# smarticle12.net
KiCad netlist of a schematic drawn in EAGLE
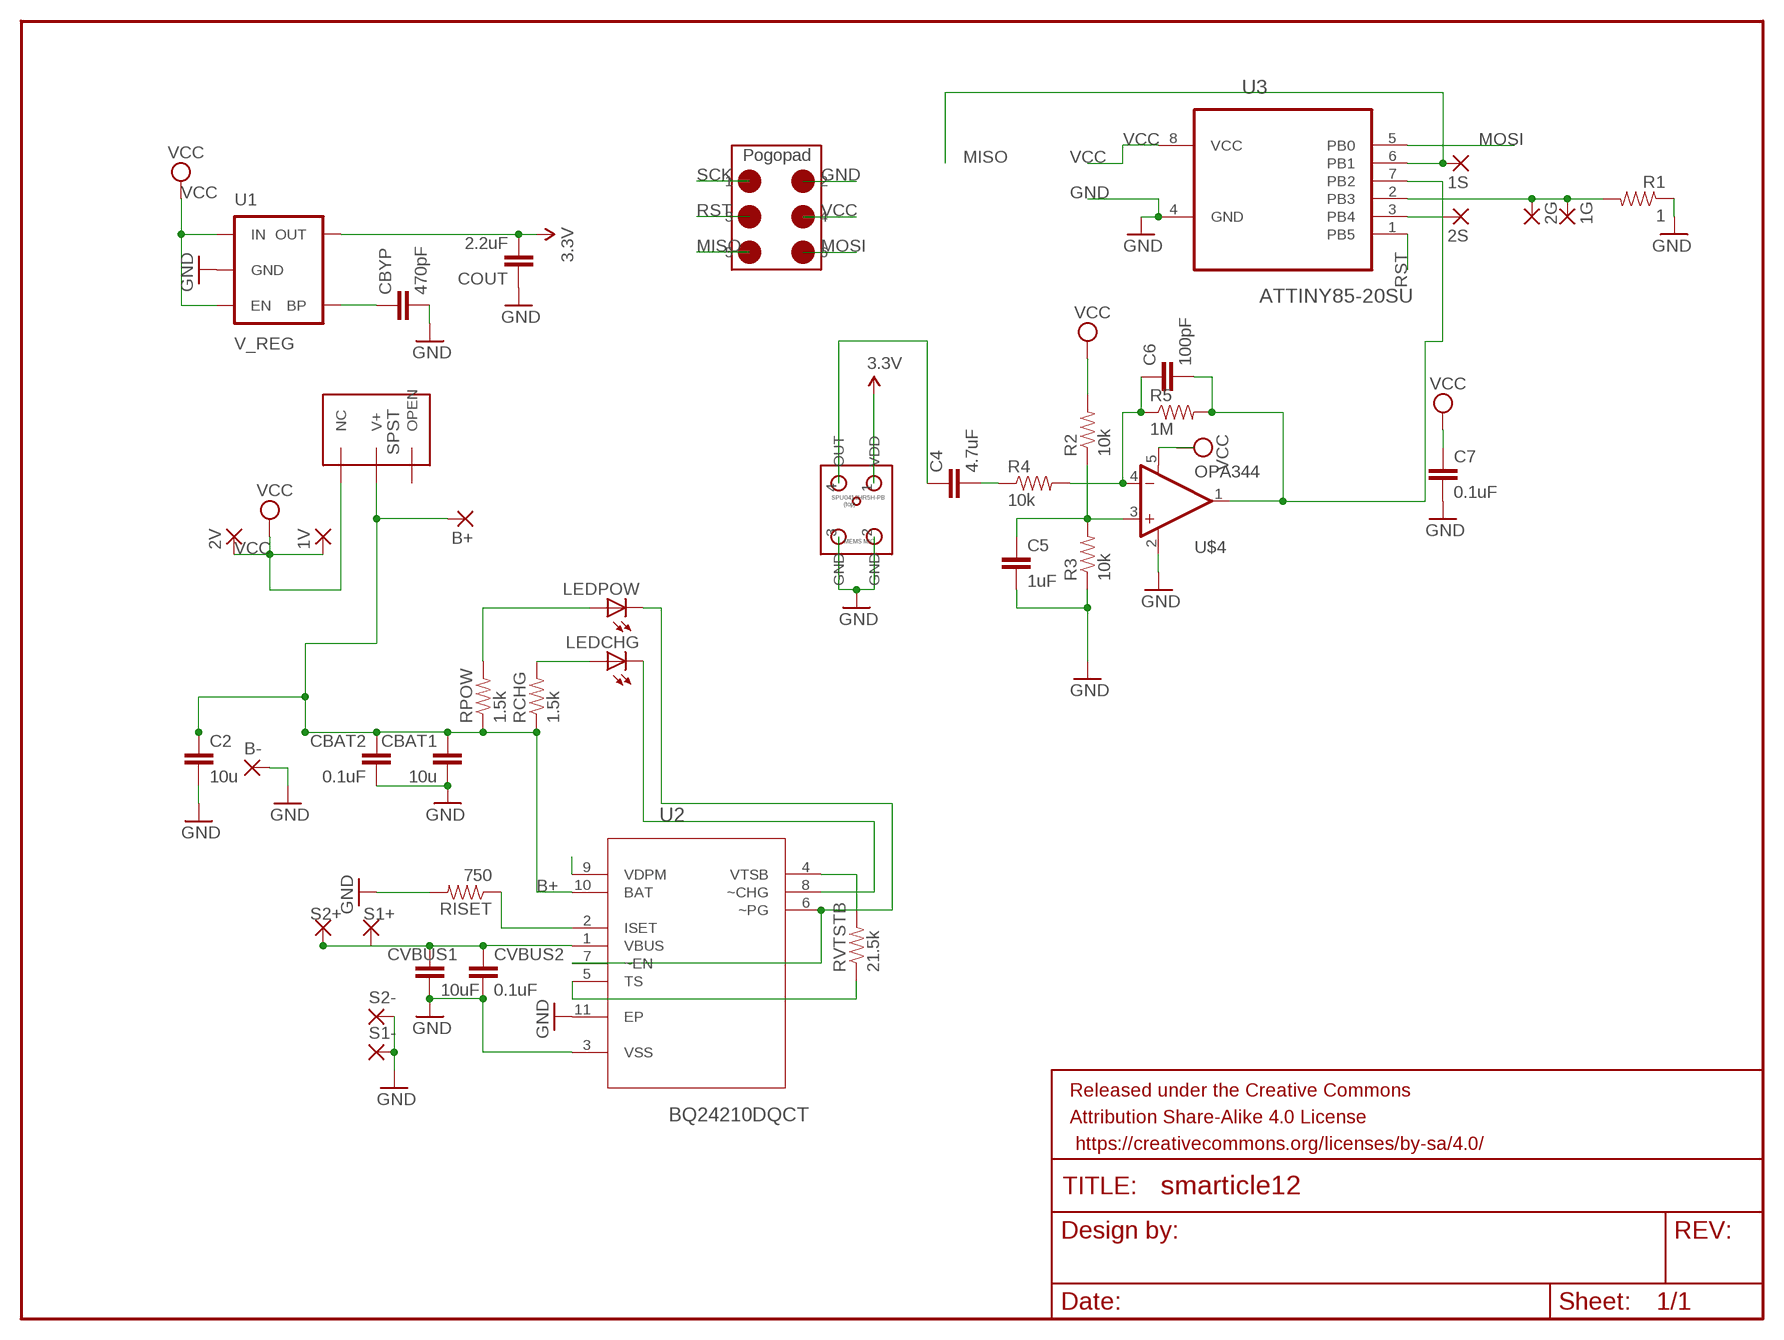
[diagram p0: schematic, sheet 1]

(export (version "E")
  (design (tool "Eeschema 10.0.6"))
  (components
    (comp (ref "1G")
      (value "1,6/0,8")
      (footprint "eagle-import:1,6_0,8")
      (libsource (lib "eagle-import") (part "1,6/0,8"))
    )
    (comp (ref "1S")
      (value "1,6/0,8")
      (footprint "eagle-import:1,6_0,8")
      (libsource (lib "eagle-import") (part "1,6/0,8"))
    )
    (comp (ref "1V")
      (value "1,6/0,8")
      (footprint "eagle-import:1,6_0,8")
      (libsource (lib "eagle-import") (part "1,6/0,8"))
    )
    (comp (ref "2G")
      (value "1,6/0,8")
      (footprint "eagle-import:1,6_0,8")
      (libsource (lib "eagle-import") (part "1,6/0,8"))
    )
    (comp (ref "2S")
      (value "1,6/0,8")
      (footprint "eagle-import:1,6_0,8")
      (libsource (lib "eagle-import") (part "1,6/0,8"))
    )
    (comp (ref "2V")
      (value "1,6/0,8")
      (footprint "eagle-import:1,6_0,8")
      (libsource (lib "eagle-import") (part "1,6/0,8"))
    )
    (comp (ref "B+")
      (value "1,6/0,8")
      (footprint "eagle-import:1,6_0,8")
      (libsource (lib "eagle-import") (part "1,6/0,8"))
    )
    (comp (ref "B-")
      (value "1,6/0,8")
      (footprint "eagle-import:1,6_0,8")
      (libsource (lib "eagle-import") (part "1,6/0,8"))
    )
    (comp (ref "C2")
      (value "10u")
      (footprint "eagle-import:0603-CAP")
      (libsource (lib "eagle-import") (part "CAP0603-CAP"))
    )
    (comp (ref "C4")
      (value "4.7uF")
      (footprint "eagle-import:0603-CAP")
      (libsource (lib "eagle-import") (part "CAP0603-CAP"))
    )
    (comp (ref "C5")
      (value "1uF")
      (footprint "eagle-import:0603-CAP")
      (libsource (lib "eagle-import") (part "CAP0603-CAP"))
    )
    (comp (ref "C6")
      (value "100pF")
      (footprint "eagle-import:0603-CAP")
      (libsource (lib "eagle-import") (part "CAP0603-CAP"))
    )
    (comp (ref "C7")
      (value "0.1uF")
      (footprint "eagle-import:0603-CAP")
      (libsource (lib "eagle-import") (part "CAP0603-CAP"))
    )
    (comp (ref "CBAT1")
      (value "10u")
      (footprint "eagle-import:0805")
      (libsource (lib "eagle-import") (part "CAP0805"))
    )
    (comp (ref "CBAT2")
      (value "0.1uF")
      (footprint "eagle-import:0603-CAP")
      (libsource (lib "eagle-import") (part "CAP0603-CAP"))
    )
    (comp (ref "CBYP")
      (value "470pF")
      (footprint "eagle-import:0603-CAP")
      (libsource (lib "eagle-import") (part "CAP0603-CAP"))
    )
    (comp (ref "COUT")
      (value "2.2uF")
      (footprint "eagle-import:0603-CAP")
      (libsource (lib "eagle-import") (part "CAP0603-CAP"))
    )
    (comp (ref "CVBUS1")
      (value "10uF")
      (footprint "eagle-import:1206")
      (libsource (lib "eagle-import") (part "CAP1206"))
    )
    (comp (ref "CVBUS2")
      (value "0.1uF")
      (footprint "eagle-import:0603-CAP")
      (libsource (lib "eagle-import") (part "CAP0603-CAP"))
    )
    (comp (ref "FRAME1")
      (value "FRAME-LETTERNO_PACKAGE")
      (footprint "eagle-import:DUMMY")
      (fields (field (name "DESIGNER") "Nobody"))
      (libsource (lib "eagle-import") (part "FRAME-LETTERNO_PACKAGE"))
    )
    (comp (ref "LEDCHG")
      (value "LEDCHIPLED_0603")
      (footprint "eagle-import:CHIPLED_0603")
      (libsource (lib "eagle-import") (part "LEDCHIPLED_0603"))
    )
    (comp (ref "LEDPOW")
      (value "LEDCHIPLED_0603")
      (footprint "eagle-import:CHIPLED_0603")
      (libsource (lib "eagle-import") (part "LEDCHIPLED_0603"))
    )
    (comp (ref "R1")
      (value "1")
      (footprint "eagle-import:0805")
      (libsource (lib "eagle-import") (part "SparkFun-Resistors_RESISTOR0805-RES"))
    )
    (comp (ref "R2")
      (value "10k")
      (footprint "eagle-import:0603-RES")
      (libsource (lib "eagle-import") (part "RESISTOR0603-RES"))
    )
    (comp (ref "R3")
      (value "10k")
      (footprint "eagle-import:0603-RES")
      (libsource (lib "eagle-import") (part "RESISTOR0603-RES"))
    )
    (comp (ref "R4")
      (value "10k")
      (footprint "eagle-import:0603-RES")
      (libsource (lib "eagle-import") (part "RESISTOR0603-RES"))
    )
    (comp (ref "R5")
      (value "1M")
      (footprint "eagle-import:0603-RES")
      (libsource (lib "eagle-import") (part "RESISTOR0603-RES"))
    )
    (comp (ref "RCHG")
      (value "1.5k")
      (footprint "eagle-import:0603-RES")
      (libsource (lib "eagle-import") (part "RESISTOR0603-RES"))
    )
    (comp (ref "RISET")
      (value "750")
      (footprint "eagle-import:0603-RES")
      (libsource (lib "eagle-import") (part "RESISTOR0603-RES"))
    )
    (comp (ref "RPOW")
      (value "1.5k")
      (footprint "eagle-import:0603-RES")
      (libsource (lib "eagle-import") (part "RESISTOR0603-RES"))
    )
    (comp (ref "RVTSTB")
      (value "21.5k")
      (footprint "eagle-import:0603-RES")
      (libsource (lib "eagle-import") (part "RESISTOR0603-RES"))
    )
    (comp (ref "S1+")
      (value "1,6/0,8")
      (footprint "eagle-import:1,6_0,8")
      (libsource (lib "eagle-import") (part "1,6/0,8"))
    )
    (comp (ref "S1-")
      (value "1,6/0,8")
      (footprint "eagle-import:1,6_0,8")
      (libsource (lib "eagle-import") (part "1,6/0,8"))
    )
    (comp (ref "S2+")
      (value "1,6/0,8")
      (footprint "eagle-import:1,6_0,8")
      (libsource (lib "eagle-import") (part "1,6/0,8"))
    )
    (comp (ref "S2-")
      (value "1,6/0,8")
      (footprint "eagle-import:1,6_0,8")
      (libsource (lib "eagle-import") (part "1,6/0,8"))
    )
    (comp (ref "U$1")
      (value "2X3POGOPADS")
      (footprint "eagle-import:3X2POGOPADS")
      (libsource (lib "eagle-import") (part "2X3POGOPADS"))
    )
    (comp (ref "U$2")
      (value "WILL_SWITCH")
      (footprint "eagle-import:WILL-SWITCH")
      (libsource (lib "eagle-import") (part "WILL_SWITCH"))
    )
    (comp (ref "U$3")
      (value "MEMSMICRO")
      (footprint "eagle-import:MEMSMIC")
      (libsource (lib "eagle-import") (part "MEMSMICRO"))
    )
    (comp (ref "U$4")
      (value "OPA344")
      (footprint "eagle-import:SOT23-5")
      (libsource (lib "eagle-import") (part "OPA344"))
    )
    (comp (ref "U1")
      (value "V_REG")
      (footprint "eagle-import:SOT23-5")
      (libsource (lib "eagle-import") (part "V_REG_LDOSMD"))
    )
    (comp (ref "U2")
      (value "BQ24210DQCT")
      (footprint "eagle-import:SON50P200X300X80-11N")
      (libsource (lib "eagle-import") (part "BQ24210DQCT"))
    )
    (comp (ref "U3")
      (value "ATTINY85-20SU")
      (footprint "eagle-import:SOIC127P798X216-8N")
      (libsource (lib "eagle-import") (part "ATTINY85-20SU"))
    )
  )
  (nets
    (net (code "1") (name "/B+") (class "Default")
      (node (ref "B+") (pin "1") (pinfunction "P_1") (pintype "passive"))
      (node (ref "C2") (pin "1") (pinfunction "1_1") (pintype "passive"))
      (node (ref "CBAT1") (pin "1") (pinfunction "1_1") (pintype "passive"))
      (node (ref "CBAT2") (pin "1") (pinfunction "1_1") (pintype "passive"))
      (node (ref "RCHG") (pin "1") (pinfunction "1_1") (pintype "passive"))
      (node (ref "RPOW") (pin "1") (pinfunction "1_1") (pintype "passive"))
      (node (ref "U$2") (pin "V+") (pinfunction "V+_V+") (pintype "bidirectional"))
      (node (ref "U2") (pin "10") (pinfunction "BAT_10") (pintype "bidirectional"))
    )
    (net (code "2") (name "/MISO") (class "Default")
      (node (ref "1S") (pin "1") (pinfunction "P_1") (pintype "passive"))
      (node (ref "U$1") (pin "5") (pinfunction "5_5") (pintype "bidirectional"))
      (node (ref "U3") (pin "6") (pinfunction "PB1_6") (pintype "bidirectional"))
    )
    (net (code "3") (name "/MOSI") (class "Default")
      (node (ref "U$1") (pin "6") (pinfunction "6_6") (pintype "bidirectional"))
      (node (ref "U3") (pin "5") (pinfunction "PB0_5") (pintype "bidirectional"))
    )
    (net (code "4") (name "/RST") (class "Default")
      (node (ref "U$1") (pin "3") (pinfunction "3_3") (pintype "bidirectional"))
      (node (ref "U3") (pin "1") (pinfunction "PB5_1") (pintype "bidirectional"))
    )
    (net (code "5") (name "/SCK") (class "Default")
      (node (ref "C6") (pin "2") (pinfunction "2_2") (pintype "passive"))
      (node (ref "R5") (pin "2") (pinfunction "2_2") (pintype "passive"))
      (node (ref "U$1") (pin "1") (pinfunction "1_1") (pintype "bidirectional"))
      (node (ref "U$4") (pin "1") (pinfunction "OUT_1") (pintype "output"))
      (node (ref "U3") (pin "7") (pinfunction "PB2_7") (pintype "bidirectional"))
    )
    (net (code "6") (name "3.3V") (class "Default")
      (node (ref "COUT") (pin "2") (pinfunction "2_2") (pintype "passive"))
      (node (ref "U$3") (pin "1") (pinfunction "VDD_1") (pintype "bidirectional"))
      (node (ref "U1") (pin "5") (pinfunction "OUT_5") (pintype "passive"))
    )
    (net (code "7") (name "GND") (class "Default")
      (node (ref "B-") (pin "1") (pinfunction "P_1") (pintype "passive"))
      (node (ref "C2") (pin "2") (pinfunction "2_2") (pintype "passive"))
      (node (ref "C5") (pin "2") (pinfunction "2_2") (pintype "passive"))
      (node (ref "C7") (pin "2") (pinfunction "2_2") (pintype "passive"))
      (node (ref "CBAT1") (pin "2") (pinfunction "2_2") (pintype "passive"))
      (node (ref "CBAT2") (pin "2") (pinfunction "2_2") (pintype "passive"))
      (node (ref "CBYP") (pin "2") (pinfunction "2_2") (pintype "passive"))
      (node (ref "COUT") (pin "1") (pinfunction "1_1") (pintype "passive"))
      (node (ref "CVBUS1") (pin "2") (pinfunction "2_2") (pintype "passive"))
      (node (ref "CVBUS2") (pin "2") (pinfunction "2_2") (pintype "passive"))
      (node (ref "R1") (pin "1") (pinfunction "1_1") (pintype "passive"))
      (node (ref "R3") (pin "1") (pinfunction "1_1") (pintype "passive"))
      (node (ref "RISET") (pin "2") (pinfunction "2_2") (pintype "passive"))
      (node (ref "S1-") (pin "1") (pinfunction "P_1") (pintype "passive"))
      (node (ref "S2-") (pin "1") (pinfunction "P_1") (pintype "passive"))
      (node (ref "U$1") (pin "2") (pinfunction "2_2") (pintype "bidirectional"))
      (node (ref "U$3") (pin "2") (pinfunction "GND_2") (pintype "bidirectional"))
      (node (ref "U$3") (pin "3") (pinfunction "GND_3") (pintype "bidirectional"))
      (node (ref "U$4") (pin "2") (pinfunction "V-_2") (pintype "power_in"))
      (node (ref "U1") (pin "2") (pinfunction "GND_2") (pintype "input"))
      (node (ref "U2") (pin "11") (pinfunction "EP_11") (pintype "passive"))
      (node (ref "U2") (pin "3") (pinfunction "VSS_3") (pintype "passive"))
      (node (ref "U3") (pin "4") (pinfunction "GND_4") (pintype "passive"))
    )
    (net (code "8") (name "Net-(1G-P)") (class "Default")
      (node (ref "1G") (pin "1") (pinfunction "P_1") (pintype "passive"))
      (node (ref "2G") (pin "1") (pinfunction "P_1") (pintype "passive"))
      (node (ref "R1") (pin "2") (pinfunction "2_2") (pintype "passive"))
      (node (ref "U3") (pin "2") (pinfunction "PB3_2") (pintype "bidirectional"))
    )
    (net (code "9") (name "Net-(2S-P)") (class "Default")
      (node (ref "2S") (pin "1") (pinfunction "P_1") (pintype "passive"))
      (node (ref "U3") (pin "3") (pinfunction "PB4_3") (pintype "bidirectional"))
    )
    (net (code "10") (name "Net-(C4-Pad2)") (class "Default")
      (node (ref "C4") (pin "2") (pinfunction "2_2") (pintype "passive"))
      (node (ref "R4") (pin "1") (pinfunction "1_1") (pintype "passive"))
    )
    (net (code "11") (name "Net-(LEDCHG-PadA)") (class "Default")
      (node (ref "LEDCHG") (pin "A") (pinfunction "A_A") (pintype "passive"))
      (node (ref "RCHG") (pin "2") (pinfunction "2_2") (pintype "passive"))
    )
    (net (code "12") (name "Net-(LEDPOW-PadA)") (class "Default")
      (node (ref "LEDPOW") (pin "A") (pinfunction "A_A") (pintype "passive"))
      (node (ref "RPOW") (pin "2") (pinfunction "2_2") (pintype "passive"))
    )
    (net (code "13") (name "Net-(S1+-P)") (class "Default")
      (node (ref "CVBUS1") (pin "1") (pinfunction "1_1") (pintype "passive"))
      (node (ref "CVBUS2") (pin "1") (pinfunction "1_1") (pintype "passive"))
      (node (ref "S1+") (pin "1") (pinfunction "P_1") (pintype "passive"))
      (node (ref "S2+") (pin "1") (pinfunction "P_1") (pintype "passive"))
      (node (ref "U2") (pin "1") (pinfunction "VBUS_1") (pintype "bidirectional"))
    )
    (net (code "14") (name "Net-(U$3-OUT)") (class "Default")
      (node (ref "C4") (pin "1") (pinfunction "1_1") (pintype "passive"))
      (node (ref "U$3") (pin "4") (pinfunction "OUT_4") (pintype "bidirectional"))
    )
    (net (code "15") (name "Net-(U$4-+IN)") (class "Default")
      (node (ref "C5") (pin "1") (pinfunction "1_1") (pintype "passive"))
      (node (ref "R2") (pin "1") (pinfunction "1_1") (pintype "passive"))
      (node (ref "R3") (pin "2") (pinfunction "2_2") (pintype "passive"))
      (node (ref "U$4") (pin "3") (pinfunction "+IN_3") (pintype "input"))
    )
    (net (code "16") (name "Net-(U$4--IN)") (class "Default")
      (node (ref "C6") (pin "1") (pinfunction "1_1") (pintype "passive"))
      (node (ref "R4") (pin "2") (pinfunction "2_2") (pintype "passive"))
      (node (ref "R5") (pin "1") (pinfunction "1_1") (pintype "passive"))
      (node (ref "U$4") (pin "4") (pinfunction "-IN_4") (pintype "input"))
    )
    (net (code "17") (name "Net-(U1-BP)") (class "Default")
      (node (ref "CBYP") (pin "1") (pinfunction "1_1") (pintype "passive"))
      (node (ref "U1") (pin "4") (pinfunction "BP_4") (pintype "input"))
    )
    (net (code "18") (name "Net-(U2-ISET)") (class "Default")
      (node (ref "RISET") (pin "1") (pinfunction "1_1") (pintype "passive"))
      (node (ref "U2") (pin "2") (pinfunction "ISET_2") (pintype "input"))
    )
    (net (code "19") (name "Net-(U2-TS)") (class "Default")
      (node (ref "RVTSTB") (pin "1") (pinfunction "1_1") (pintype "passive"))
      (node (ref "U2") (pin "5") (pinfunction "TS_5") (pintype "input"))
    )
    (net (code "20") (name "Net-(U2-VTSB)") (class "Default")
      (node (ref "RVTSTB") (pin "2") (pinfunction "2_2") (pintype "passive"))
      (node (ref "U2") (pin "4") (pinfunction "VTSB_4") (pintype "output"))
    )
    (net (code "21") (name "Net-(U2-~{CHG})") (class "Default")
      (node (ref "LEDCHG") (pin "C") (pinfunction "C_C") (pintype "passive"))
      (node (ref "U2") (pin "8") (pinfunction "~{CHG}_8") (pintype "output"))
    )
    (net (code "22") (name "Net-(U2-~{EN})") (class "Default")
      (node (ref "LEDPOW") (pin "C") (pinfunction "C_C") (pintype "passive"))
      (node (ref "U2") (pin "6") (pinfunction "~{PG}_6") (pintype "output"))
      (node (ref "U2") (pin "7") (pinfunction "~{EN}_7") (pintype "input"))
    )
    (net (code "23") (name "VCC") (class "Default")
      (node (ref "1V") (pin "1") (pinfunction "P_1") (pintype "passive"))
      (node (ref "2V") (pin "1") (pinfunction "P_1") (pintype "passive"))
      (node (ref "C7") (pin "1") (pinfunction "1_1") (pintype "passive"))
      (node (ref "R2") (pin "2") (pinfunction "2_2") (pintype "passive"))
      (node (ref "U$1") (pin "4") (pinfunction "4_4") (pintype "bidirectional"))
      (node (ref "U$2") (pin "NC") (pinfunction "NC_NC") (pintype "bidirectional"))
      (node (ref "U$4") (pin "5") (pinfunction "V+_5") (pintype "power_in"))
      (node (ref "U1") (pin "1") (pinfunction "IN_1") (pintype "input"))
      (node (ref "U1") (pin "3") (pinfunction "EN_3") (pintype "input"))
      (node (ref "U3") (pin "8") (pinfunction "VCC_8") (pintype "power_in"))
    )
    (net (code "24") (name "unconnected-(U$2-PadOPEN)") (class "Default")
      (node (ref "U$2") (pin "OPEN") (pinfunction "OPEN_OPEN") (pintype "bidirectional"))
    )
    (net (code "25") (name "unconnected-(U2-VDPM-Pad9)") (class "Default")
      (node (ref "U2") (pin "9") (pinfunction "VDPM_9") (pintype "input"))
    )
  )
)
